# DVT-Atlas-Driver1.net
KiCad netlist of a schematic drawn in Altium Designer
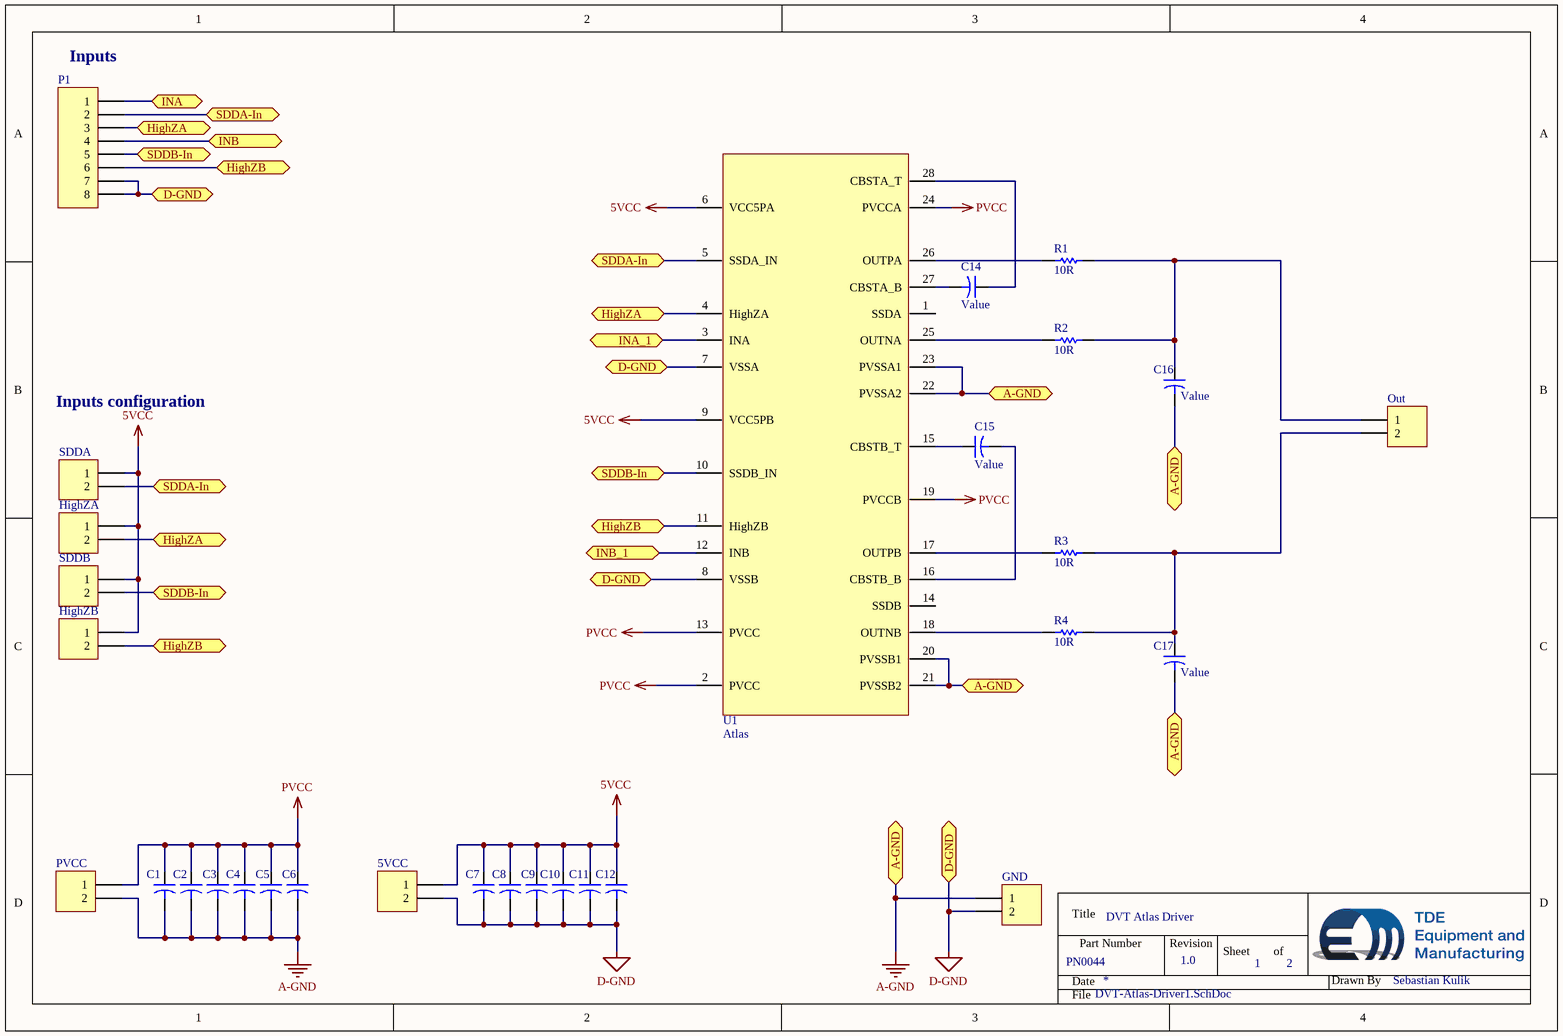
[diagram p0: DVT-Atlas-Driver1.SchDoc]

(export (version "E")
  (design (tool "Eeschema 10.0.6"))
  (components
    (comp (ref "*") (value "Om") (footprint "Om-5mm") (libsource (lib "ICs") (part "Om")))
    (comp (ref "+") (value "Om") (footprint "Om-5mm") (libsource (lib "ICs") (part "Om")))
    (comp (ref "5VCC")
      (value "PHOENIX_1715721")
      (footprint "Phoenix-2-5_08")
      (description "Phoenix, 2 pol, 5.08mm, 22A, 715721")
      (fields (field (name "MANUFACTURER") "Phoenix") (field (name "PUBLISHER") "Sebastian Kulik"))
      (libsource (lib "Connectors") (part "2Pol_1715721"))
    )
    (comp (ref "C1")
      (value "Capacitor-Dummy-THT")
      (footprint "Dummy-10mm")
      (fields (field (name "PUBLISHER") "Sebastian Kulik"))
      (libsource (lib "Capacitors") (part "Capacitor-Dummy-THT"))
    )
    (comp (ref "C2")
      (value "Capacitor-Dummy-THT")
      (footprint "KEMET-C052H")
      (fields (field (name "PUBLISHER") "Sebastian Kulik"))
      (libsource (lib "Capacitors") (part "Capacitor-Dummy-THT"))
    )
    (comp (ref "C3")
      (value "Capacitor-Dummy-THT")
      (footprint "KEMET-C052H")
      (fields (field (name "PUBLISHER") "Sebastian Kulik"))
      (libsource (lib "Capacitors") (part "Capacitor-Dummy-THT"))
    )
    (comp (ref "C4")
      (value "Capacitor-Dummy-THT")
      (footprint "KEMET-C052H")
      (fields (field (name "PUBLISHER") "Sebastian Kulik"))
      (libsource (lib "Capacitors") (part "Capacitor-Dummy-THT"))
    )
    (comp (ref "C5")
      (value "Capacitor-Dummy-THT")
      (footprint "KEMET-C052H")
      (fields (field (name "PUBLISHER") "Sebastian Kulik"))
      (libsource (lib "Capacitors") (part "Capacitor-Dummy-THT"))
    )
    (comp (ref "C6")
      (value "Capacitor-Dummy-THT")
      (footprint "KEMET-C052H")
      (fields (field (name "PUBLISHER") "Sebastian Kulik"))
      (libsource (lib "Capacitors") (part "Capacitor-Dummy-THT"))
    )
    (comp (ref "C7")
      (value "Capacitor-Dummy-THT")
      (footprint "KEMET-C052H")
      (fields (field (name "PUBLISHER") "Sebastian Kulik"))
      (libsource (lib "Capacitors") (part "Capacitor-Dummy-THT"))
    )
    (comp (ref "C8")
      (value "Capacitor-Dummy-THT")
      (footprint "Dummy-10mm")
      (fields (field (name "PUBLISHER") "Sebastian Kulik"))
      (libsource (lib "Capacitors") (part "Capacitor-Dummy-THT"))
    )
    (comp (ref "C9")
      (value "Capacitor-Dummy-THT")
      (footprint "KEMET-C052H")
      (fields (field (name "PUBLISHER") "Sebastian Kulik"))
      (libsource (lib "Capacitors") (part "Capacitor-Dummy-THT"))
    )
    (comp (ref "C10")
      (value "Capacitor-Dummy-THT")
      (footprint "KEMET-C052H")
      (fields (field (name "PUBLISHER") "Sebastian Kulik"))
      (libsource (lib "Capacitors") (part "Capacitor-Dummy-THT"))
    )
    (comp (ref "C11")
      (value "Capacitor-Dummy-THT")
      (footprint "KEMET-C052H")
      (fields (field (name "PUBLISHER") "Sebastian Kulik"))
      (libsource (lib "Capacitors") (part "Capacitor-Dummy-THT"))
    )
    (comp (ref "C12")
      (value "Capacitor-Dummy-THT")
      (footprint "KEMET-C052H")
      (fields (field (name "PUBLISHER") "Sebastian Kulik"))
      (libsource (lib "Capacitors") (part "Capacitor-Dummy-THT"))
    )
    (comp (ref "C14")
      (value "Value")
      (footprint "KEMET-C052H")
      (description "Capacitor-Dummy-THT")
      (fields (field (name "PUBLISHER") "Sebastian Kulik"))
      (libsource (lib "Capacitors") (part "Capacitor-Dummy-THT"))
    )
    (comp (ref "C15")
      (value "Value")
      (footprint "KEMET-C052H")
      (description "Capacitor-Dummy-THT")
      (fields (field (name "PUBLISHER") "Sebastian Kulik"))
      (libsource (lib "Capacitors") (part "Capacitor-Dummy-THT"))
    )
    (comp (ref "C16")
      (value "Value")
      (footprint "KEMET-C052H")
      (description "Capacitor-Dummy-THT")
      (fields (field (name "PUBLISHER") "Sebastian Kulik"))
      (libsource (lib "Capacitors") (part "Capacitor-Dummy-THT"))
    )
    (comp (ref "C17")
      (value "Value")
      (footprint "KEMET-C052H")
      (description "Capacitor-Dummy-THT")
      (fields (field (name "PUBLISHER") "Sebastian Kulik"))
      (libsource (lib "Capacitors") (part "Capacitor-Dummy-THT"))
    )
    (comp (ref "GND")
      (value "PHOENIX_1715721")
      (footprint "Phoenix-2-5_08")
      (description "Phoenix, 2 pol, 5.08mm, 22A, 715721")
      (fields (field (name "MANUFACTURER") "Phoenix") (field (name "PUBLISHER") "Sebastian Kulik"))
      (libsource (lib "") (part "2Pol_1715721_1"))
    )
    (comp (ref "HighZA")
      (value "Plug_2_180_2.54")
      (footprint "HDR1X2")
      (description "Plug, 2-Pin")
      (fields (field (name "MANUFACTURER") "WE") (field (name "PUBLISHER") "Sebastian Kulik"))
      (libsource (lib "Connectors") (part "Plug_2_180_2.54"))
    )
    (comp (ref "HighZB")
      (value "Plug_2_180_2.54")
      (footprint "HDR1X2")
      (description "Plug, 2-Pin")
      (fields (field (name "MANUFACTURER") "WE") (field (name "PUBLISHER") "Sebastian Kulik"))
      (libsource (lib "Connectors") (part "Plug_2_180_2.54"))
    )
    (comp (ref "Out")
      (value "PHOENIX_1715721")
      (footprint "Phoenix-2-5_08")
      (description "Phoenix, 2 pol, 5.08mm, 22A, 715721")
      (fields (field (name "MANUFACTURER") "Phoenix") (field (name "PUBLISHER") "Sebastian Kulik"))
      (libsource (lib "") (part "2Pol_1715721_1"))
    )
    (comp (ref "P1")
      (value "Plug_08_2.54")
      (footprint "HDR1X8_2.54")
      (description "Plug, 08-Pin")
      (fields (field (name "MANUFACTURER") "WE") (field (name "PUBLISHER") "Sebastian Kulik"))
      (libsource (lib "Connectors") (part "Plug_08_2.54"))
    )
    (comp (ref "PVCC")
      (value "PHOENIX_1715721")
      (footprint "Phoenix-2-5_08")
      (description "Phoenix, 2 pol, 5.08mm, 22A, 715721")
      (fields (field (name "MANUFACTURER") "Phoenix") (field (name "PUBLISHER") "Sebastian Kulik"))
      (libsource (lib "Connectors") (part "2Pol_1715721"))
    )
    (comp (ref "R1")
      (value "10R")
      (footprint "Dummy-10mm")
      (description "Vishay RN60 series,175°C ,250mW, 1%")
      (fields
        (field (name "MANUFACTURER") "Vishay")
        (field (name "Comment") "10R_10mm-HT-THT")
        (field (name "PUBLISHER") "Sebastian Kulik")
      )
      (libsource (lib "Resistors") (part "10R_10mm-HT-THT"))
    )
    (comp (ref "R2")
      (value "10R")
      (footprint "Dummy-10mm")
      (description "Vishay RN60 series,175°C ,250mW, 1%")
      (fields
        (field (name "MANUFACTURER") "Vishay")
        (field (name "Comment") "10R_10mm-HT-THT")
        (field (name "PUBLISHER") "Sebastian Kulik")
      )
      (libsource (lib "Resistors") (part "10R_10mm-HT-THT"))
    )
    (comp (ref "R3")
      (value "10R")
      (footprint "Dummy-10mm")
      (description "Vishay RN60 series,175°C ,250mW, 1%")
      (fields
        (field (name "MANUFACTURER") "Vishay")
        (field (name "Comment") "10R_10mm-HT-THT")
        (field (name "PUBLISHER") "Sebastian Kulik")
      )
      (libsource (lib "Resistors") (part "10R_10mm-HT-THT"))
    )
    (comp (ref "R4")
      (value "10R")
      (footprint "Dummy-10mm")
      (description "Vishay RN60 series,175°C ,250mW, 1%")
      (fields
        (field (name "MANUFACTURER") "Vishay")
        (field (name "Comment") "10R_10mm-HT-THT")
        (field (name "PUBLISHER") "Sebastian Kulik")
      )
      (libsource (lib "Resistors") (part "10R_10mm-HT-THT"))
    )
    (comp (ref "SDDA")
      (value "Plug_2_180_2.54")
      (footprint "HDR1X2")
      (description "Plug, 2-Pin")
      (fields (field (name "MANUFACTURER") "WE") (field (name "PUBLISHER") "Sebastian Kulik"))
      (libsource (lib "Connectors") (part "Plug_2_180_2.54"))
    )
    (comp (ref "SDDB")
      (value "Plug_2_180_2.54")
      (footprint "HDR1X2")
      (description "Plug, 2-Pin")
      (fields (field (name "MANUFACTURER") "WE") (field (name "PUBLISHER") "Sebastian Kulik"))
      (libsource (lib "Connectors") (part "Plug_2_180_2.54"))
    )
    (comp (ref "U1")
      (value "Atlas")
      (footprint "SOIC28")
      (description "Gate driver, 30V, HT")
      (fields (field (name "MANUFACTURER") "CISSOID") (field (name "PUBLISHER") "Sebastian Kulik"))
      (libsource (lib "ICs") (part "CHT_TIT3345E_CSOIC28_T"))
    )
  )
  (nets
    (net (code "1") (name "/HighZA") (class "Default")
      (node (ref "HighZA") (pin "2") (pinfunction "2_2") (pintype "passive"))
      (node (ref "P1") (pin "3") (pinfunction "3_3") (pintype "passive"))
      (node (ref "U1") (pin "4") (pinfunction "HighZA_4") (pintype "passive"))
    )
    (net (code "2") (name "/HighZB") (class "Default")
      (node (ref "HighZB") (pin "2") (pinfunction "2_2") (pintype "passive"))
      (node (ref "P1") (pin "6") (pinfunction "6_6") (pintype "passive"))
      (node (ref "U1") (pin "11") (pinfunction "HighZB_11") (pintype "passive"))
    )
    (net (code "3") (name "/INA") (class "Default")
      (node (ref "P1") (pin "1") (pinfunction "1_1") (pintype "passive"))
    )
    (net (code "4") (name "/INA_1") (class "Default")
      (node (ref "U1") (pin "3") (pinfunction "INA_3") (pintype "passive"))
    )
    (net (code "5") (name "/INB") (class "Default")
      (node (ref "P1") (pin "4") (pinfunction "4_4") (pintype "passive"))
    )
    (net (code "6") (name "/INB_1") (class "Default")
      (node (ref "U1") (pin "12") (pinfunction "INB_12") (pintype "passive"))
    )
    (net (code "7") (name "/SDDA-In") (class "Default")
      (node (ref "P1") (pin "2") (pinfunction "2_2") (pintype "passive"))
      (node (ref "SDDA") (pin "2") (pinfunction "2_2") (pintype "passive"))
      (node (ref "U1") (pin "5") (pinfunction "SSDA_IN_5") (pintype "passive"))
    )
    (net (code "8") (name "/SDDB-In") (class "Default")
      (node (ref "P1") (pin "5") (pinfunction "5_5") (pintype "passive"))
      (node (ref "SDDB") (pin "2") (pinfunction "2_2") (pintype "passive"))
      (node (ref "U1") (pin "10") (pinfunction "SSDB_IN_10") (pintype "passive"))
    )
    (net (code "9") (name "5VCC") (class "Default")
      (node (ref "5VCC") (pin "1") (pinfunction "1_1") (pintype "passive"))
      (node (ref "C10") (pin "1") (pinfunction "1_1") (pintype "passive"))
      (node (ref "C11") (pin "1") (pinfunction "1_1") (pintype "passive"))
      (node (ref "C12") (pin "1") (pinfunction "1_1") (pintype "passive"))
      (node (ref "C7") (pin "1") (pinfunction "1_1") (pintype "passive"))
      (node (ref "C8") (pin "1") (pinfunction "1_1") (pintype "passive"))
      (node (ref "C9") (pin "1") (pinfunction "1_1") (pintype "passive"))
      (node (ref "HighZA") (pin "1") (pinfunction "1_1") (pintype "passive"))
      (node (ref "HighZB") (pin "1") (pinfunction "1_1") (pintype "passive"))
      (node (ref "SDDA") (pin "1") (pinfunction "1_1") (pintype "passive"))
      (node (ref "SDDB") (pin "1") (pinfunction "1_1") (pintype "passive"))
      (node (ref "U1") (pin "6") (pinfunction "VCC5PA_6") (pintype "passive"))
      (node (ref "U1") (pin "9") (pinfunction "VCC5PB_9") (pintype "passive"))
    )
    (net (code "10") (name "A-GND") (class "Default")
      (node (ref "C1") (pin "2") (pinfunction "2_2") (pintype "passive"))
      (node (ref "C16") (pin "2") (pinfunction "2_2") (pintype "passive"))
      (node (ref "C17") (pin "2") (pinfunction "2_2") (pintype "passive"))
      (node (ref "C2") (pin "2") (pinfunction "2_2") (pintype "passive"))
      (node (ref "C3") (pin "2") (pinfunction "2_2") (pintype "passive"))
      (node (ref "C4") (pin "2") (pinfunction "2_2") (pintype "passive"))
      (node (ref "C5") (pin "2") (pinfunction "2_2") (pintype "passive"))
      (node (ref "C6") (pin "2") (pinfunction "2_2") (pintype "passive"))
      (node (ref "GND") (pin "1") (pinfunction "1_1") (pintype "passive"))
      (node (ref "PVCC") (pin "2") (pinfunction "2_2") (pintype "passive"))
      (node (ref "U1") (pin "20") (pinfunction "PVSSB1_20") (pintype "power_in"))
      (node (ref "U1") (pin "21") (pinfunction "PVSSB2_21") (pintype "passive"))
      (node (ref "U1") (pin "22") (pinfunction "PVSSA2_22") (pintype "passive"))
      (node (ref "U1") (pin "23") (pinfunction "PVSSA1_23") (pintype "power_in"))
    )
    (net (code "11") (name "D-GND") (class "Default")
      (node (ref "5VCC") (pin "2") (pinfunction "2_2") (pintype "passive"))
      (node (ref "C10") (pin "2") (pinfunction "2_2") (pintype "passive"))
      (node (ref "C11") (pin "2") (pinfunction "2_2") (pintype "passive"))
      (node (ref "C12") (pin "2") (pinfunction "2_2") (pintype "passive"))
      (node (ref "C7") (pin "2") (pinfunction "2_2") (pintype "passive"))
      (node (ref "C8") (pin "2") (pinfunction "2_2") (pintype "passive"))
      (node (ref "C9") (pin "2") (pinfunction "2_2") (pintype "passive"))
      (node (ref "GND") (pin "2") (pinfunction "2_2") (pintype "passive"))
      (node (ref "P1") (pin "7") (pinfunction "7_7") (pintype "passive"))
      (node (ref "P1") (pin "8") (pinfunction "8_8") (pintype "passive"))
      (node (ref "U1") (pin "7") (pinfunction "VSSA_7") (pintype "passive"))
      (node (ref "U1") (pin "8") (pinfunction "VSSB_8") (pintype "passive"))
    )
    (net (code "12") (name "Net-(C16-Pad1)") (class "Default")
      (node (ref "C16") (pin "1") (pinfunction "1_1") (pintype "passive"))
      (node (ref "Out") (pin "1") (pinfunction "1_1") (pintype "passive"))
      (node (ref "R1") (pin "2") (pinfunction "2_2") (pintype "passive"))
      (node (ref "R2") (pin "2") (pinfunction "2_2") (pintype "passive"))
    )
    (net (code "13") (name "Net-(C17-Pad1)") (class "Default")
      (node (ref "C17") (pin "1") (pinfunction "1_1") (pintype "passive"))
      (node (ref "Out") (pin "2") (pinfunction "2_2") (pintype "passive"))
      (node (ref "R3") (pin "2") (pinfunction "2_2") (pintype "passive"))
      (node (ref "R4") (pin "2") (pinfunction "2_2") (pintype "passive"))
    )
    (net (code "14") (name "Net-(U1-CBSTA_B)") (class "Default")
      (node (ref "C14") (pin "2") (pinfunction "2_2") (pintype "passive"))
      (node (ref "U1") (pin "27") (pinfunction "CBSTA_B_27") (pintype "passive"))
    )
    (net (code "15") (name "Net-(U1-CBSTA_T)") (class "Default")
      (node (ref "C14") (pin "1") (pinfunction "1_1") (pintype "passive"))
      (node (ref "U1") (pin "28") (pinfunction "CBSTA_T_28") (pintype "power_in"))
    )
    (net (code "16") (name "Net-(U1-CBSTB_B)") (class "Default")
      (node (ref "C15") (pin "2") (pinfunction "2_2") (pintype "passive"))
      (node (ref "U1") (pin "16") (pinfunction "CBSTB_B_16") (pintype "passive"))
    )
    (net (code "17") (name "Net-(U1-CBSTB_T)") (class "Default")
      (node (ref "C15") (pin "1") (pinfunction "1_1") (pintype "passive"))
      (node (ref "U1") (pin "15") (pinfunction "CBSTB_T_15") (pintype "passive"))
    )
    (net (code "18") (name "Net-(U1-OUTNA)") (class "Default")
      (node (ref "R2") (pin "1") (pinfunction "1_1") (pintype "passive"))
      (node (ref "U1") (pin "25") (pinfunction "OUTNA_25") (pintype "passive"))
    )
    (net (code "19") (name "Net-(U1-OUTNB)") (class "Default")
      (node (ref "R4") (pin "1") (pinfunction "1_1") (pintype "passive"))
      (node (ref "U1") (pin "18") (pinfunction "OUTNB_18") (pintype "passive"))
    )
    (net (code "20") (name "Net-(U1-OUTPA)") (class "Default")
      (node (ref "R1") (pin "1") (pinfunction "1_1") (pintype "passive"))
      (node (ref "U1") (pin "26") (pinfunction "OUTPA_26") (pintype "power_in"))
    )
    (net (code "21") (name "Net-(U1-OUTPB)") (class "Default")
      (node (ref "R3") (pin "1") (pinfunction "1_1") (pintype "passive"))
      (node (ref "U1") (pin "17") (pinfunction "OUTPB_17") (pintype "power_in"))
    )
    (net (code "22") (name "PVCC") (class "Default")
      (node (ref "C1") (pin "1") (pinfunction "1_1") (pintype "passive"))
      (node (ref "C2") (pin "1") (pinfunction "1_1") (pintype "passive"))
      (node (ref "C3") (pin "1") (pinfunction "1_1") (pintype "passive"))
      (node (ref "C4") (pin "1") (pinfunction "1_1") (pintype "passive"))
      (node (ref "C5") (pin "1") (pinfunction "1_1") (pintype "passive"))
      (node (ref "C6") (pin "1") (pinfunction "1_1") (pintype "passive"))
      (node (ref "PVCC") (pin "1") (pinfunction "1_1") (pintype "passive"))
      (node (ref "U1") (pin "13") (pinfunction "PVCC_13") (pintype "passive"))
      (node (ref "U1") (pin "19") (pinfunction "PVCCB_19") (pintype "passive"))
      (node (ref "U1") (pin "2") (pinfunction "PVCC_2") (pintype "passive"))
      (node (ref "U1") (pin "24") (pinfunction "PVCCA_24") (pintype "passive"))
    )
    (net (code "23") (name "unconnected-(U1-SSDA-Pad1)") (class "Default")
      (node (ref "U1") (pin "1") (pinfunction "SSDA_1") (pintype "power_in"))
    )
    (net (code "24") (name "unconnected-(U1-SSDB-Pad14)") (class "Default")
      (node (ref "U1") (pin "14") (pinfunction "SSDB_14") (pintype "power_in"))
    )
  )
)
